# TinyBuddy-rev2.net
KiCad netlist of a schematic drawn in EAGLE
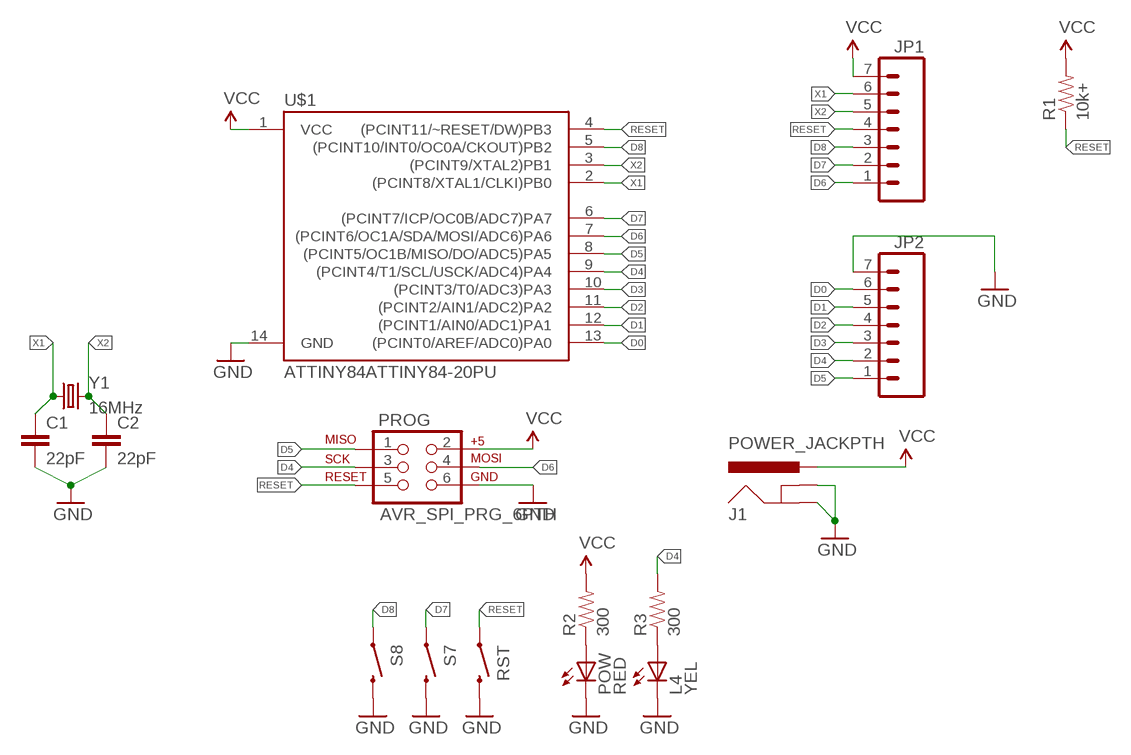
[diagram p0: schematic, sheet 1]

(export (version "E")
  (design (tool "Eeschema 10.0.6"))
  (components
    (comp (ref "C1")
      (value "22pF")
      (footprint "eagle-import:CAP-PTH-SMALL")
      (libsource (lib "eagle-import") (part "CAPPTH"))
    )
    (comp (ref "C2")
      (value "22pF")
      (footprint "eagle-import:CAP-PTH-SMALL")
      (libsource (lib "eagle-import") (part "CAPPTH"))
    )
    (comp (ref "J1")
      (value "POWER_JACKPTH")
      (footprint "eagle-import:POWER_JACK_PTH")
      (libsource (lib "eagle-import") (part "POWER_JACKPTH"))
    )
    (comp (ref "JP1")
      (value "M07NOSILK")
      (footprint "eagle-import:1X07_NOSILK")
      (libsource (lib "eagle-import") (part "M07NOSILK"))
    )
    (comp (ref "JP2")
      (value "M07NOSILK")
      (footprint "eagle-import:1X07_NOSILK")
      (libsource (lib "eagle-import") (part "M07NOSILK"))
    )
    (comp (ref "L4")
      (value "YEL")
      (footprint "eagle-import:LED3MM")
      (libsource (lib "eagle-import") (part "LED3MM"))
    )
    (comp (ref "POW")
      (value "RED")
      (footprint "eagle-import:LED3MM")
      (libsource (lib "eagle-import") (part "LED3MM"))
    )
    (comp (ref "PROG")
      (value "AVR_SPI_PRG_6PTH")
      (footprint "eagle-import:2X3")
      (libsource (lib "eagle-import") (part "AVR_SPI_PRG_6PTH"))
    )
    (comp (ref "R1")
      (value "10k+")
      (footprint "eagle-import:1_6W-RES")
      (libsource (lib "eagle-import") (part "RESISTORPTH-1/6W"))
    )
    (comp (ref "R2")
      (value "300")
      (footprint "eagle-import:1_6W-RES")
      (libsource (lib "eagle-import") (part "RESISTORPTH-1/6W"))
    )
    (comp (ref "R3")
      (value "300")
      (footprint "eagle-import:1_6W-RES")
      (libsource (lib "eagle-import") (part "RESISTORPTH-1/6W"))
    )
    (comp (ref "RST")
      (value "SWITCH-MOMENTARY-2PTH")
      (footprint "eagle-import:TACTILE-PTH")
      (libsource (lib "eagle-import") (part "SWITCH-MOMENTARY-2PTH"))
    )
    (comp (ref "S7")
      (value "SWITCH-MOMENTARY-2PTH")
      (footprint "eagle-import:TACTILE-PTH")
      (libsource (lib "eagle-import") (part "SWITCH-MOMENTARY-2PTH"))
    )
    (comp (ref "S8")
      (value "SWITCH-MOMENTARY-2PTH")
      (footprint "eagle-import:TACTILE-PTH")
      (libsource (lib "eagle-import") (part "SWITCH-MOMENTARY-2PTH"))
    )
    (comp (ref "U$1")
      (value "ATTINY84ATTINY84-20PU")
      (footprint "eagle-import:DIL14")
      (libsource (lib "eagle-import") (part "ATTINY84ATTINY84-20PU"))
    )
    (comp (ref "Y1")
      (value "16MHz")
      (footprint "eagle-import:HC49US")
      (libsource (lib "eagle-import") (part "CRYSTALHC49US"))
    )
  )
  (nets
    (net (code "1") (name "D0") (class "Default")
      (node (ref "JP2") (pin "6") (pinfunction "6_6") (pintype "passive"))
      (node (ref "U$1") (pin "13") (pinfunction "(PCINT0/AREF/ADC0)PA0_13") (pintype "bidirectional"))
    )
    (net (code "2") (name "D1") (class "Default")
      (node (ref "JP2") (pin "5") (pinfunction "5_5") (pintype "passive"))
      (node (ref "U$1") (pin "12") (pinfunction "(PCINT1/AIN0/ADC1)PA1_12") (pintype "bidirectional"))
    )
    (net (code "3") (name "D2") (class "Default")
      (node (ref "JP2") (pin "4") (pinfunction "4_4") (pintype "passive"))
      (node (ref "U$1") (pin "11") (pinfunction "(PCINT2/AIN1/ADC2)PA2_11") (pintype "bidirectional"))
    )
    (net (code "4") (name "D3") (class "Default")
      (node (ref "JP2") (pin "3") (pinfunction "3_3") (pintype "passive"))
      (node (ref "U$1") (pin "10") (pinfunction "(PCINT3/T0/ADC3)PA3_10") (pintype "bidirectional"))
    )
    (net (code "5") (name "D4") (class "Default")
      (node (ref "JP2") (pin "2") (pinfunction "2_2") (pintype "passive"))
      (node (ref "PROG") (pin "3") (pinfunction "3_3") (pintype "passive"))
      (node (ref "R3") (pin "2") (pinfunction "2_2") (pintype "passive"))
      (node (ref "U$1") (pin "9") (pinfunction "(PCINT4/T1/SCL/USCK/ADC4)PA4_9") (pintype "bidirectional"))
    )
    (net (code "6") (name "D5") (class "Default")
      (node (ref "JP2") (pin "1") (pinfunction "1_1") (pintype "passive"))
      (node (ref "PROG") (pin "1") (pinfunction "1_1") (pintype "passive"))
      (node (ref "U$1") (pin "8") (pinfunction "(PCINT5/OC1B/MISO/DO/ADC5)PA5_8") (pintype "bidirectional"))
    )
    (net (code "7") (name "D6") (class "Default")
      (node (ref "JP1") (pin "1") (pinfunction "1_1") (pintype "passive"))
      (node (ref "PROG") (pin "4") (pinfunction "4_4") (pintype "passive"))
      (node (ref "U$1") (pin "7") (pinfunction "(PCINT6/OC1A/SDA/MOSI/ADC6)PA6_7") (pintype "bidirectional"))
    )
    (net (code "8") (name "D7") (class "Default")
      (node (ref "JP1") (pin "2") (pinfunction "2_2") (pintype "passive"))
      (node (ref "S7") (pin "1") (pinfunction "1_1") (pintype "passive"))
      (node (ref "U$1") (pin "6") (pinfunction "(PCINT7/ICP/OC0B/ADC7)PA7_6") (pintype "bidirectional"))
    )
    (net (code "9") (name "D8") (class "Default")
      (node (ref "JP1") (pin "3") (pinfunction "3_3") (pintype "passive"))
      (node (ref "S8") (pin "1") (pinfunction "1_1") (pintype "passive"))
      (node (ref "U$1") (pin "5") (pinfunction "(PCINT10/INT0/OC0A/CKOUT)PB2_5") (pintype "bidirectional"))
    )
    (net (code "10") (name "GND") (class "Default")
      (node (ref "C1") (pin "2") (pinfunction "2_2") (pintype "passive"))
      (node (ref "C2") (pin "2") (pinfunction "2_2") (pintype "passive"))
      (node (ref "J1") (pin "GND") (pinfunction "GND_GND") (pintype "bidirectional"))
      (node (ref "J1") (pin "GNDBREAK") (pinfunction "GNDBREAK_GNDBREAK") (pintype "bidirectional"))
      (node (ref "JP2") (pin "7") (pinfunction "7_7") (pintype "passive"))
      (node (ref "L4") (pin "K") (pinfunction "C_K") (pintype "passive"))
      (node (ref "POW") (pin "K") (pinfunction "C_K") (pintype "passive"))
      (node (ref "PROG") (pin "6") (pinfunction "6_6") (pintype "passive"))
      (node (ref "RST") (pin "3") (pinfunction "2_3") (pintype "passive"))
      (node (ref "S7") (pin "3") (pinfunction "2_3") (pintype "passive"))
      (node (ref "S8") (pin "3") (pinfunction "2_3") (pintype "passive"))
      (node (ref "U$1") (pin "14") (pinfunction "GND_14") (pintype "bidirectional"))
    )
    (net (code "11") (name "Net-(L4-PadA)") (class "Default")
      (node (ref "L4") (pin "A") (pinfunction "A_A") (pintype "passive"))
      (node (ref "R3") (pin "1") (pinfunction "1_1") (pintype "passive"))
    )
    (net (code "12") (name "Net-(POW-PadA)") (class "Default")
      (node (ref "POW") (pin "A") (pinfunction "A_A") (pintype "passive"))
      (node (ref "R2") (pin "1") (pinfunction "1_1") (pintype "passive"))
    )
    (net (code "13") (name "RESET") (class "Default")
      (node (ref "JP1") (pin "4") (pinfunction "4_4") (pintype "passive"))
      (node (ref "PROG") (pin "5") (pinfunction "5_5") (pintype "passive"))
      (node (ref "R1") (pin "1") (pinfunction "1_1") (pintype "passive"))
      (node (ref "RST") (pin "1") (pinfunction "1_1") (pintype "passive"))
      (node (ref "U$1") (pin "4") (pinfunction "(PCINT11/~{RESET/DW})PB3_4") (pintype "bidirectional"))
    )
    (net (code "14") (name "VCC") (class "Default")
      (node (ref "J1") (pin "PWR") (pinfunction "PWR_PWR") (pintype "bidirectional"))
      (node (ref "JP1") (pin "7") (pinfunction "7_7") (pintype "passive"))
      (node (ref "PROG") (pin "2") (pinfunction "2_2") (pintype "passive"))
      (node (ref "R1") (pin "2") (pinfunction "2_2") (pintype "passive"))
      (node (ref "R2") (pin "2") (pinfunction "2_2") (pintype "passive"))
      (node (ref "U$1") (pin "1") (pinfunction "VCC_1") (pintype "bidirectional"))
    )
    (net (code "15") (name "X1") (class "Default")
      (node (ref "C1") (pin "1") (pinfunction "1_1") (pintype "passive"))
      (node (ref "JP1") (pin "6") (pinfunction "6_6") (pintype "passive"))
      (node (ref "U$1") (pin "2") (pinfunction "(PCINT8/XTAL1/CLKI)PB0_2") (pintype "bidirectional"))
      (node (ref "Y1") (pin "1") (pinfunction "1_1") (pintype "passive"))
    )
    (net (code "16") (name "X2") (class "Default")
      (node (ref "C2") (pin "1") (pinfunction "1_1") (pintype "passive"))
      (node (ref "JP1") (pin "5") (pinfunction "5_5") (pintype "passive"))
      (node (ref "U$1") (pin "3") (pinfunction "(PCINT9/XTAL2)PB1_3") (pintype "bidirectional"))
      (node (ref "Y1") (pin "2") (pinfunction "2_2") (pintype "passive"))
    )
  )
)
